# EEM_CONN.net
KiCad netlist of a schematic drawn in Altium Designer
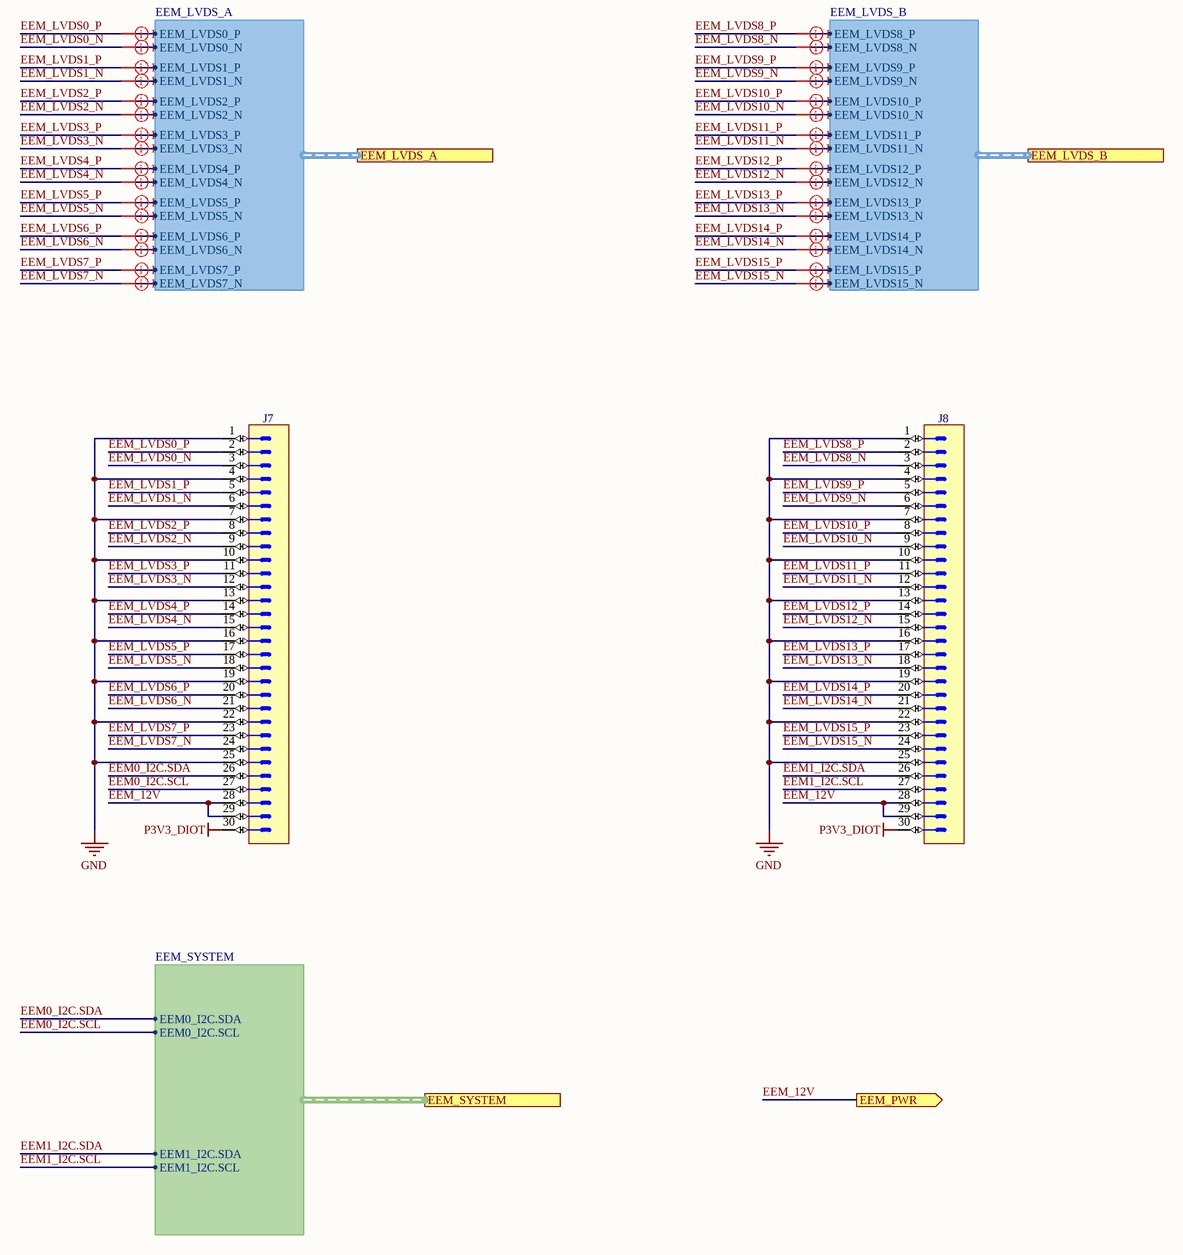
[diagram p0: EEM_CONN.SchDoc]

(export (version "E")
  (design (tool "Eeschema 10.0.6"))
  (components
    (comp (ref "J7")
      (value "~")
      (footprint "3M_N2530-6002RB")
      (description "Connector 30 Male")
      (fields
        (field (name "PART NUMBER") "3M_N2530-6002RB")
        (field (name "MANUFACTURER") "3M")
        (field (name "AUTHOR") "CERN DEM JLC")
      )
      (libsource (lib "Connectors") (part "Connector 30 Male"))
    )
    (comp (ref "J8")
      (value "~")
      (footprint "3M_N2530-6002RB")
      (description "Connector 30 Male")
      (fields
        (field (name "PART NUMBER") "3M_N2530-6002RB")
        (field (name "MANUFACTURER") "3M")
        (field (name "AUTHOR") "CERN DEM JLC")
      )
      (libsource (lib "Connectors") (part "Connector 30 Male"))
    )
  )
  (nets
    (net (code "4") (name "/EEM0_I2C.SCL") (class "Default")
      (node (ref "J7") (pin "27") (pinfunction "27_27") (pintype "bidirectional"))
    )
    (net (code "5") (name "/EEM0_I2C.SDA") (class "Default")
      (node (ref "J7") (pin "26") (pinfunction "26_26") (pintype "bidirectional"))
    )
    (net (code "6") (name "/EEM1_I2C.SCL") (class "Default")
      (node (ref "J8") (pin "27") (pinfunction "27_27") (pintype "bidirectional"))
    )
    (net (code "7") (name "/EEM1_I2C.SDA") (class "Default")
      (node (ref "J8") (pin "26") (pinfunction "26_26") (pintype "bidirectional"))
    )
    (net (code "8") (name "/EEM_12V") (class "Default")
      (node (ref "J7") (pin "28") (pinfunction "28_28") (pintype "bidirectional"))
      (node (ref "J7") (pin "29") (pinfunction "29_29") (pintype "bidirectional"))
      (node (ref "J8") (pin "28") (pinfunction "28_28") (pintype "bidirectional"))
      (node (ref "J8") (pin "29") (pinfunction "29_29") (pintype "bidirectional"))
    )
    (net (code "9") (name "/EEM_LVDS0_N") (class "Default")
      (node (ref "J7") (pin "3") (pinfunction "3_3") (pintype "bidirectional"))
    )
    (net (code "10") (name "/EEM_LVDS0_P") (class "Default")
      (node (ref "J7") (pin "2") (pinfunction "2_2") (pintype "bidirectional"))
    )
    (net (code "11") (name "/EEM_LVDS1_N") (class "Default")
      (node (ref "J7") (pin "6") (pinfunction "6_6") (pintype "bidirectional"))
    )
    (net (code "12") (name "/EEM_LVDS1_P") (class "Default")
      (node (ref "J7") (pin "5") (pinfunction "5_5") (pintype "bidirectional"))
    )
    (net (code "13") (name "/EEM_LVDS2_N") (class "Default")
      (node (ref "J7") (pin "9") (pinfunction "9_9") (pintype "bidirectional"))
    )
    (net (code "14") (name "/EEM_LVDS2_P") (class "Default")
      (node (ref "J7") (pin "8") (pinfunction "8_8") (pintype "bidirectional"))
    )
    (net (code "15") (name "/EEM_LVDS3_N") (class "Default")
      (node (ref "J7") (pin "12") (pinfunction "12_12") (pintype "bidirectional"))
    )
    (net (code "16") (name "/EEM_LVDS3_P") (class "Default")
      (node (ref "J7") (pin "11") (pinfunction "11_11") (pintype "bidirectional"))
    )
    (net (code "17") (name "/EEM_LVDS4_N") (class "Default")
      (node (ref "J7") (pin "15") (pinfunction "15_15") (pintype "bidirectional"))
    )
    (net (code "18") (name "/EEM_LVDS4_P") (class "Default")
      (node (ref "J7") (pin "14") (pinfunction "14_14") (pintype "bidirectional"))
    )
    (net (code "19") (name "/EEM_LVDS5_N") (class "Default")
      (node (ref "J7") (pin "18") (pinfunction "18_18") (pintype "bidirectional"))
    )
    (net (code "20") (name "/EEM_LVDS5_P") (class "Default")
      (node (ref "J7") (pin "17") (pinfunction "17_17") (pintype "bidirectional"))
    )
    (net (code "21") (name "/EEM_LVDS6_N") (class "Default")
      (node (ref "J7") (pin "21") (pinfunction "21_21") (pintype "bidirectional"))
    )
    (net (code "22") (name "/EEM_LVDS6_P") (class "Default")
      (node (ref "J7") (pin "20") (pinfunction "20_20") (pintype "bidirectional"))
    )
    (net (code "23") (name "/EEM_LVDS7_N") (class "Default")
      (node (ref "J7") (pin "24") (pinfunction "24_24") (pintype "bidirectional"))
    )
    (net (code "24") (name "/EEM_LVDS7_P") (class "Default")
      (node (ref "J7") (pin "23") (pinfunction "23_23") (pintype "bidirectional"))
    )
    (net (code "25") (name "/EEM_LVDS8_N") (class "Default")
      (node (ref "J8") (pin "3") (pinfunction "3_3") (pintype "bidirectional"))
    )
    (net (code "26") (name "/EEM_LVDS8_P") (class "Default")
      (node (ref "J8") (pin "2") (pinfunction "2_2") (pintype "bidirectional"))
    )
    (net (code "27") (name "/EEM_LVDS9_N") (class "Default")
      (node (ref "J8") (pin "6") (pinfunction "6_6") (pintype "bidirectional"))
    )
    (net (code "28") (name "/EEM_LVDS9_P") (class "Default")
      (node (ref "J8") (pin "5") (pinfunction "5_5") (pintype "bidirectional"))
    )
    (net (code "29") (name "/EEM_LVDS10_N") (class "Default")
      (node (ref "J8") (pin "9") (pinfunction "9_9") (pintype "bidirectional"))
    )
    (net (code "30") (name "/EEM_LVDS10_P") (class "Default")
      (node (ref "J8") (pin "8") (pinfunction "8_8") (pintype "bidirectional"))
    )
    (net (code "31") (name "/EEM_LVDS11_N") (class "Default")
      (node (ref "J8") (pin "12") (pinfunction "12_12") (pintype "bidirectional"))
    )
    (net (code "32") (name "/EEM_LVDS11_P") (class "Default")
      (node (ref "J8") (pin "11") (pinfunction "11_11") (pintype "bidirectional"))
    )
    (net (code "33") (name "/EEM_LVDS12_N") (class "Default")
      (node (ref "J8") (pin "15") (pinfunction "15_15") (pintype "bidirectional"))
    )
    (net (code "34") (name "/EEM_LVDS12_P") (class "Default")
      (node (ref "J8") (pin "14") (pinfunction "14_14") (pintype "bidirectional"))
    )
    (net (code "35") (name "/EEM_LVDS13_N") (class "Default")
      (node (ref "J8") (pin "18") (pinfunction "18_18") (pintype "bidirectional"))
    )
    (net (code "36") (name "/EEM_LVDS13_P") (class "Default")
      (node (ref "J8") (pin "17") (pinfunction "17_17") (pintype "bidirectional"))
    )
    (net (code "37") (name "/EEM_LVDS14_N") (class "Default")
      (node (ref "J8") (pin "21") (pinfunction "21_21") (pintype "bidirectional"))
    )
    (net (code "38") (name "/EEM_LVDS14_P") (class "Default")
      (node (ref "J8") (pin "20") (pinfunction "20_20") (pintype "bidirectional"))
    )
    (net (code "39") (name "/EEM_LVDS15_N") (class "Default")
      (node (ref "J8") (pin "24") (pinfunction "24_24") (pintype "bidirectional"))
    )
    (net (code "40") (name "/EEM_LVDS15_P") (class "Default")
      (node (ref "J8") (pin "23") (pinfunction "23_23") (pintype "bidirectional"))
    )
    (net (code "44") (name "GND") (class "Default")
      (node (ref "J7") (pin "1") (pinfunction "1_1") (pintype "bidirectional"))
      (node (ref "J7") (pin "10") (pinfunction "10_10") (pintype "bidirectional"))
      (node (ref "J7") (pin "13") (pinfunction "13_13") (pintype "bidirectional"))
      (node (ref "J7") (pin "16") (pinfunction "16_16") (pintype "bidirectional"))
      (node (ref "J7") (pin "19") (pinfunction "19_19") (pintype "bidirectional"))
      (node (ref "J7") (pin "22") (pinfunction "22_22") (pintype "bidirectional"))
      (node (ref "J7") (pin "25") (pinfunction "25_25") (pintype "bidirectional"))
      (node (ref "J7") (pin "4") (pinfunction "4_4") (pintype "bidirectional"))
      (node (ref "J7") (pin "7") (pinfunction "7_7") (pintype "bidirectional"))
      (node (ref "J8") (pin "1") (pinfunction "1_1") (pintype "bidirectional"))
      (node (ref "J8") (pin "10") (pinfunction "10_10") (pintype "bidirectional"))
      (node (ref "J8") (pin "13") (pinfunction "13_13") (pintype "bidirectional"))
      (node (ref "J8") (pin "16") (pinfunction "16_16") (pintype "bidirectional"))
      (node (ref "J8") (pin "19") (pinfunction "19_19") (pintype "bidirectional"))
      (node (ref "J8") (pin "22") (pinfunction "22_22") (pintype "bidirectional"))
      (node (ref "J8") (pin "25") (pinfunction "25_25") (pintype "bidirectional"))
      (node (ref "J8") (pin "4") (pinfunction "4_4") (pintype "bidirectional"))
      (node (ref "J8") (pin "7") (pinfunction "7_7") (pintype "bidirectional"))
    )
    (net (code "45") (name "P3V3_DIOT") (class "Default")
      (node (ref "J7") (pin "30") (pinfunction "30_30") (pintype "bidirectional"))
      (node (ref "J8") (pin "30") (pinfunction "30_30") (pintype "bidirectional"))
    )
  )
)
